# romboard_v2.net
KiCad netlist of a schematic drawn in EAGLE
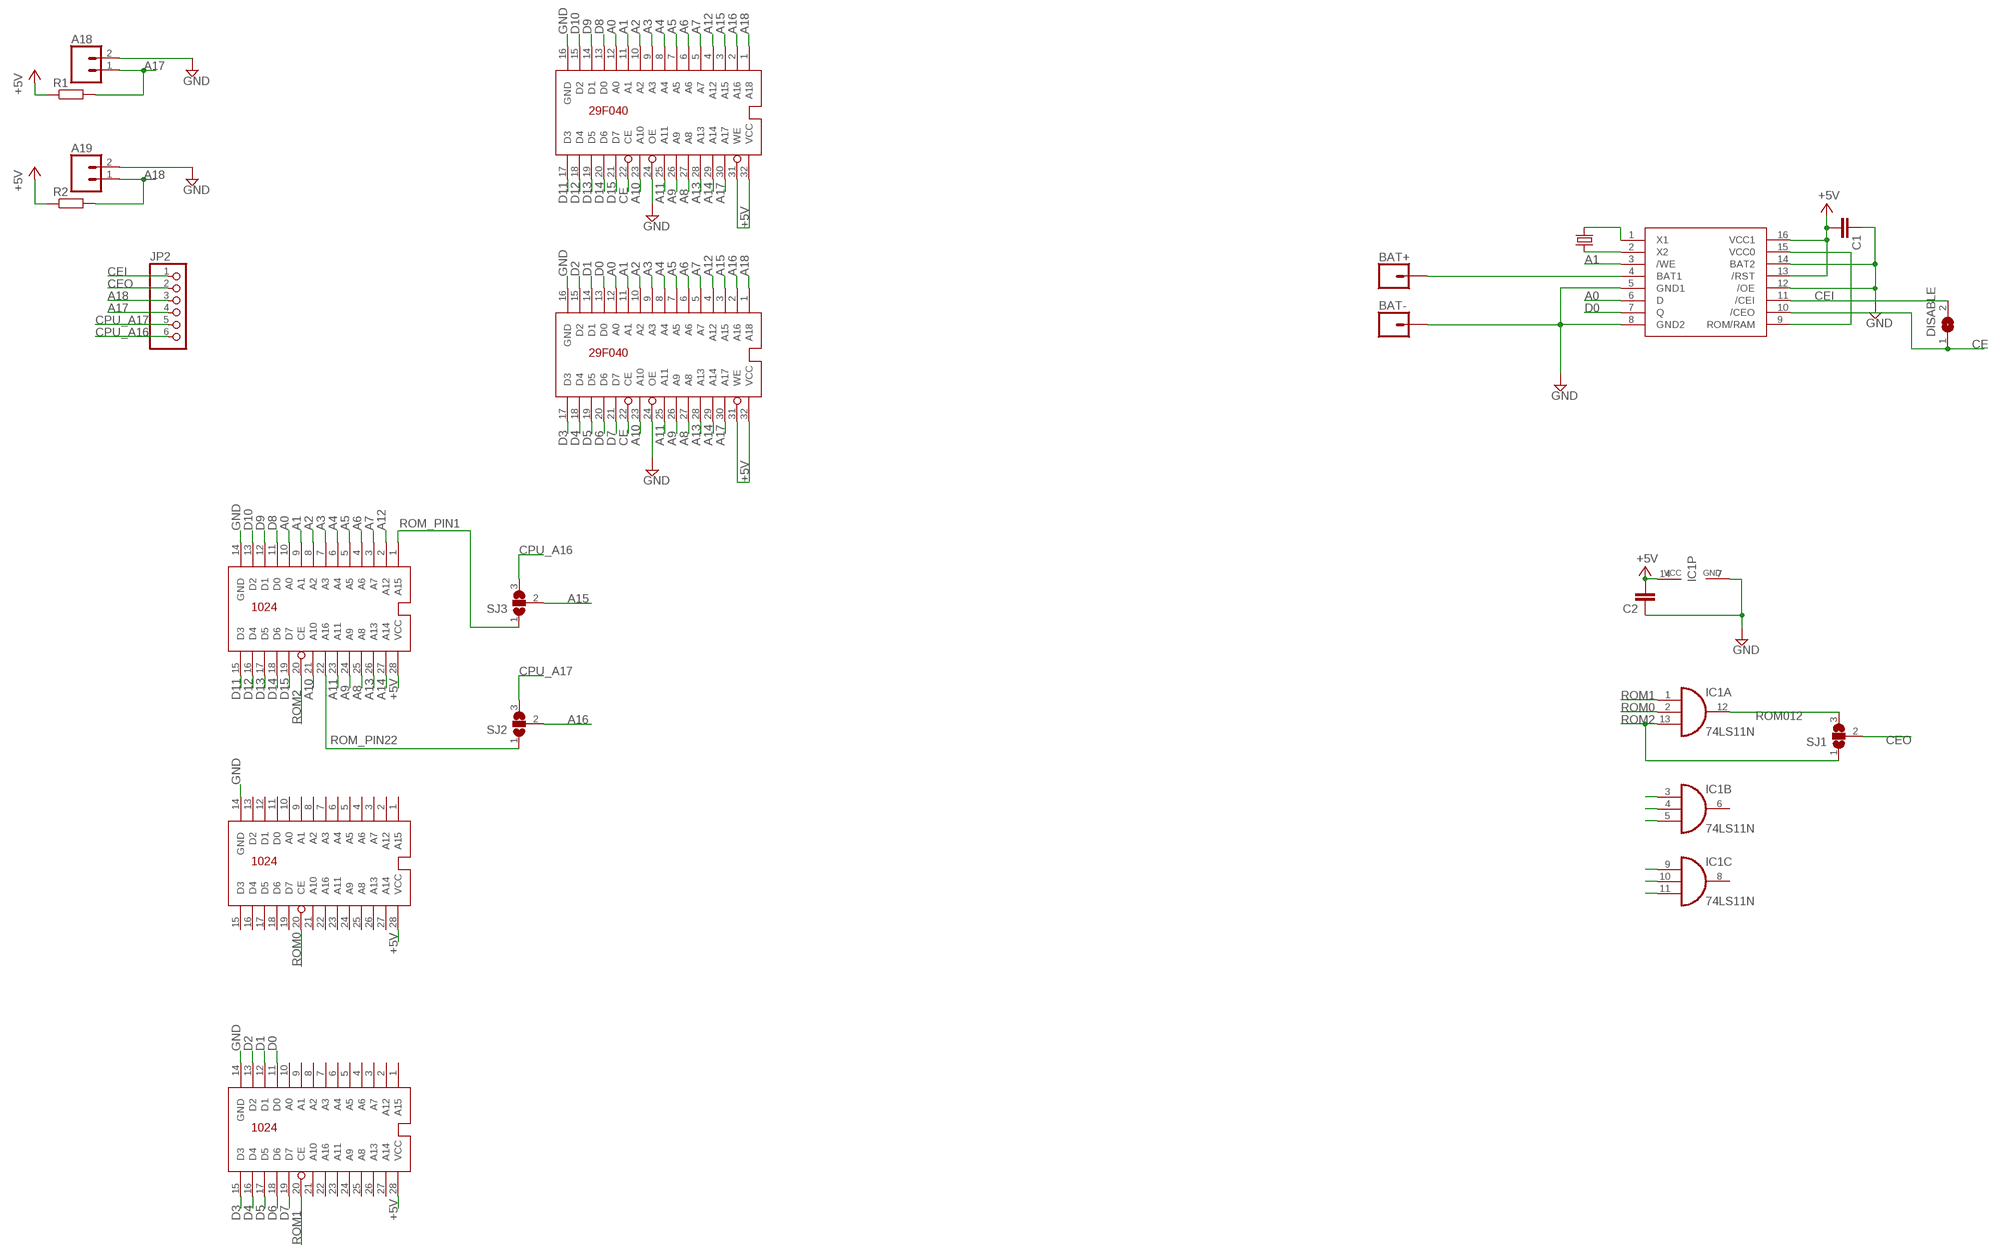
[diagram p0: schematic, sheet 1]

(export (version "E")
  (design (tool "Eeschema 10.0.6"))
  (components
    (comp (ref "32.768KHZ")
      (value "CRYSTALTC38H")
      (footprint "eagle-import:TC38H")
      (libsource (lib "eagle-import") (part "CRYSTALTC38H"))
    )
    (comp (ref "A18")
      (value "CONN_02")
      (footprint "eagle-import:1X02")
      (libsource (lib "eagle-import") (part "CONN_02"))
    )
    (comp (ref "A19")
      (value "CONN_02")
      (footprint "eagle-import:1X02")
      (libsource (lib "eagle-import") (part "CONN_02"))
    )
    (comp (ref "BAT+")
      (value "CONN_01")
      (footprint "eagle-import:1X01")
      (libsource (lib "eagle-import") (part "CONN_01"))
    )
    (comp (ref "BAT-")
      (value "CONN_01")
      (footprint "eagle-import:1X01")
      (libsource (lib "eagle-import") (part "CONN_01"))
    )
    (comp (ref "C1")
      (value "C-EU050-025X075")
      (footprint "eagle-import:C050-025X075")
      (libsource (lib "eagle-import") (part "C-EU050-025X075"))
    )
    (comp (ref "C2")
      (value "C-EU050-025X075")
      (footprint "eagle-import:C050-025X075")
      (libsource (lib "eagle-import") (part "C-EU050-025X075"))
    )
    (comp (ref "DISABLE")
      (value "SJ")
      (footprint "eagle-import:SJ")
      (libsource (lib "eagle-import") (part "SJ"))
    )
    (comp (ref "HI0_SOCKET")
      (value "ROM1024")
      (footprint "eagle-import:ROM28PIN")
      (libsource (lib "eagle-import") (part "ROM1024"))
    )
    (comp (ref "IC1")
      (value "74LS11N")
      (footprint "eagle-import:DIL14")
      (libsource (lib "eagle-import") (part "7411NLS"))
    )
    (comp (ref "JP2")
      (value "PINHD-1X6/90")
      (footprint "eagle-import:1X06_90")
      (libsource (lib "eagle-import") (part "PINHD-1X6/90"))
    )
    (comp (ref "LO2_SOCKET")
      (value "ROM1024")
      (footprint "eagle-import:ROM28PIN")
      (libsource (lib "eagle-import") (part "ROM1024"))
    )
    (comp (ref "LO2_SOCKET1")
      (value "ROM1024")
      (footprint "eagle-import:ROM28PIN")
      (libsource (lib "eagle-import") (part "ROM1024"))
    )
    (comp (ref "R1")
      (value "R-EU_0207/12")
      (footprint "eagle-import:0207_12")
      (libsource (lib "eagle-import") (part "R-EU_0207/12"))
    )
    (comp (ref "R2")
      (value "R-EU_0207/12")
      (footprint "eagle-import:0207_12")
      (libsource (lib "eagle-import") (part "R-EU_0207/12"))
    )
    (comp (ref "SJ1")
      (value "SJ2W")
      (footprint "eagle-import:SJ_2")
      (libsource (lib "eagle-import") (part "SJ2W"))
    )
    (comp (ref "SJ2")
      (value "SJ2W")
      (footprint "eagle-import:SJ_2")
      (libsource (lib "eagle-import") (part "SJ2W"))
    )
    (comp (ref "SJ3")
      (value "SJ2W")
      (footprint "eagle-import:SJ_2")
      (libsource (lib "eagle-import") (part "SJ2W"))
    )
    (comp (ref "U$1")
      (value "AM29F040")
      (footprint "eagle-import:AM29F040")
      (libsource (lib "eagle-import") (part "AM29F040"))
    )
    (comp (ref "U$2")
      (value "AM29F040")
      (footprint "eagle-import:AM29F040")
      (libsource (lib "eagle-import") (part "AM29F040"))
    )
    (comp (ref "U$4")
      (value "DS1315")
      (footprint "eagle-import:DIL16")
      (libsource (lib "eagle-import") (part "DS1315"))
    )
  )
  (nets
    (net (code "1") (name "+5V") (class "Default")
      (node (ref "C1") (pin "2") (pinfunction "2_2") (pintype "passive"))
      (node (ref "C2") (pin "2") (pinfunction "2_2") (pintype "passive"))
      (node (ref "HI0_SOCKET") (pin "28") (pinfunction "VCC_28") (pintype "bidirectional"))
      (node (ref "IC1") (pin "14") (pinfunction "VCC_14") (pintype "power_in"))
      (node (ref "LO2_SOCKET") (pin "28") (pinfunction "VCC_28") (pintype "bidirectional"))
      (node (ref "LO2_SOCKET1") (pin "28") (pinfunction "VCC_28") (pintype "bidirectional"))
      (node (ref "R1") (pin "1") (pinfunction "1_1") (pintype "passive"))
      (node (ref "R2") (pin "1") (pinfunction "1_1") (pintype "passive"))
      (node (ref "U$1") (pin "31") (pinfunction "WE_31") (pintype "bidirectional"))
      (node (ref "U$1") (pin "32") (pinfunction "VCC_32") (pintype "bidirectional"))
      (node (ref "U$2") (pin "31") (pinfunction "WE_31") (pintype "bidirectional"))
      (node (ref "U$2") (pin "32") (pinfunction "VCC_32") (pintype "bidirectional"))
      (node (ref "U$4") (pin "13") (pinfunction "/RST_13") (pintype "bidirectional"))
      (node (ref "U$4") (pin "16") (pinfunction "VCC1_16") (pintype "bidirectional"))
    )
    (net (code "2") (name "/A0") (class "Default")
      (node (ref "HI0_SOCKET") (pin "10") (pinfunction "A0_10") (pintype "bidirectional"))
      (node (ref "U$1") (pin "12") (pinfunction "A0_12") (pintype "bidirectional"))
      (node (ref "U$2") (pin "12") (pinfunction "A0_12") (pintype "bidirectional"))
      (node (ref "U$4") (pin "6") (pinfunction "D_6") (pintype "bidirectional"))
    )
    (net (code "3") (name "/A1") (class "Default")
      (node (ref "HI0_SOCKET") (pin "9") (pinfunction "A1_9") (pintype "bidirectional"))
      (node (ref "U$1") (pin "11") (pinfunction "A1_11") (pintype "bidirectional"))
      (node (ref "U$2") (pin "11") (pinfunction "A1_11") (pintype "bidirectional"))
      (node (ref "U$4") (pin "3") (pinfunction "/WE_3") (pintype "bidirectional"))
    )
    (net (code "4") (name "/A2") (class "Default")
      (node (ref "HI0_SOCKET") (pin "8") (pinfunction "A2_8") (pintype "bidirectional"))
      (node (ref "U$1") (pin "10") (pinfunction "A2_10") (pintype "bidirectional"))
      (node (ref "U$2") (pin "10") (pinfunction "A2_10") (pintype "bidirectional"))
    )
    (net (code "5") (name "/A3") (class "Default")
      (node (ref "HI0_SOCKET") (pin "7") (pinfunction "A3_7") (pintype "bidirectional"))
      (node (ref "U$1") (pin "9") (pinfunction "A3_9") (pintype "bidirectional"))
      (node (ref "U$2") (pin "9") (pinfunction "A3_9") (pintype "bidirectional"))
    )
    (net (code "6") (name "/A4") (class "Default")
      (node (ref "HI0_SOCKET") (pin "6") (pinfunction "A4_6") (pintype "bidirectional"))
      (node (ref "U$1") (pin "8") (pinfunction "A4_8") (pintype "bidirectional"))
      (node (ref "U$2") (pin "8") (pinfunction "A4_8") (pintype "bidirectional"))
    )
    (net (code "7") (name "/A5") (class "Default")
      (node (ref "HI0_SOCKET") (pin "5") (pinfunction "A5_5") (pintype "bidirectional"))
      (node (ref "U$1") (pin "7") (pinfunction "A5_7") (pintype "bidirectional"))
      (node (ref "U$2") (pin "7") (pinfunction "A5_7") (pintype "bidirectional"))
    )
    (net (code "8") (name "/A6") (class "Default")
      (node (ref "HI0_SOCKET") (pin "4") (pinfunction "A6_4") (pintype "bidirectional"))
      (node (ref "U$1") (pin "6") (pinfunction "A6_6") (pintype "bidirectional"))
      (node (ref "U$2") (pin "6") (pinfunction "A6_6") (pintype "bidirectional"))
    )
    (net (code "9") (name "/A7") (class "Default")
      (node (ref "HI0_SOCKET") (pin "3") (pinfunction "A7_3") (pintype "bidirectional"))
      (node (ref "U$1") (pin "5") (pinfunction "A7_5") (pintype "bidirectional"))
      (node (ref "U$2") (pin "5") (pinfunction "A7_5") (pintype "bidirectional"))
    )
    (net (code "10") (name "/A8") (class "Default")
      (node (ref "HI0_SOCKET") (pin "25") (pinfunction "A8_25") (pintype "bidirectional"))
      (node (ref "U$1") (pin "27") (pinfunction "A8_27") (pintype "bidirectional"))
      (node (ref "U$2") (pin "27") (pinfunction "A8_27") (pintype "bidirectional"))
    )
    (net (code "11") (name "/A9") (class "Default")
      (node (ref "HI0_SOCKET") (pin "24") (pinfunction "A9_24") (pintype "bidirectional"))
      (node (ref "U$1") (pin "26") (pinfunction "A9_26") (pintype "bidirectional"))
      (node (ref "U$2") (pin "26") (pinfunction "A9_26") (pintype "bidirectional"))
    )
    (net (code "12") (name "/A10") (class "Default")
      (node (ref "HI0_SOCKET") (pin "21") (pinfunction "A10_21") (pintype "bidirectional"))
      (node (ref "U$1") (pin "23") (pinfunction "A10_23") (pintype "bidirectional"))
      (node (ref "U$2") (pin "23") (pinfunction "A10_23") (pintype "bidirectional"))
    )
    (net (code "13") (name "/A11") (class "Default")
      (node (ref "HI0_SOCKET") (pin "23") (pinfunction "A11_23") (pintype "bidirectional"))
      (node (ref "U$1") (pin "25") (pinfunction "A11_25") (pintype "bidirectional"))
      (node (ref "U$2") (pin "25") (pinfunction "A11_25") (pintype "bidirectional"))
    )
    (net (code "14") (name "/A12") (class "Default")
      (node (ref "HI0_SOCKET") (pin "2") (pinfunction "A12_2") (pintype "bidirectional"))
      (node (ref "U$1") (pin "4") (pinfunction "A12_4") (pintype "bidirectional"))
      (node (ref "U$2") (pin "4") (pinfunction "A12_4") (pintype "bidirectional"))
    )
    (net (code "15") (name "/A13") (class "Default")
      (node (ref "HI0_SOCKET") (pin "26") (pinfunction "A13_26") (pintype "bidirectional"))
      (node (ref "U$1") (pin "28") (pinfunction "A13_28") (pintype "bidirectional"))
      (node (ref "U$2") (pin "28") (pinfunction "A13_28") (pintype "bidirectional"))
    )
    (net (code "16") (name "/A14") (class "Default")
      (node (ref "HI0_SOCKET") (pin "27") (pinfunction "A14_27") (pintype "bidirectional"))
      (node (ref "U$1") (pin "29") (pinfunction "A14_29") (pintype "bidirectional"))
      (node (ref "U$2") (pin "29") (pinfunction "A14_29") (pintype "bidirectional"))
    )
    (net (code "17") (name "/A15") (class "Default")
      (node (ref "SJ3") (pin "2") (pinfunction "2_2") (pintype "passive"))
      (node (ref "U$1") (pin "3") (pinfunction "A15_3") (pintype "bidirectional"))
      (node (ref "U$2") (pin "3") (pinfunction "A15_3") (pintype "bidirectional"))
    )
    (net (code "18") (name "/A16") (class "Default")
      (node (ref "SJ2") (pin "2") (pinfunction "2_2") (pintype "passive"))
      (node (ref "U$1") (pin "2") (pinfunction "A16_2") (pintype "bidirectional"))
      (node (ref "U$2") (pin "2") (pinfunction "A16_2") (pintype "bidirectional"))
    )
    (net (code "19") (name "/A17") (class "Default")
      (node (ref "A18") (pin "1") (pinfunction "1_1") (pintype "passive"))
      (node (ref "JP2") (pin "4") (pinfunction "4_4") (pintype "passive"))
      (node (ref "R1") (pin "2") (pinfunction "2_2") (pintype "passive"))
      (node (ref "U$1") (pin "30") (pinfunction "A17_30") (pintype "bidirectional"))
      (node (ref "U$2") (pin "30") (pinfunction "A17_30") (pintype "bidirectional"))
    )
    (net (code "20") (name "/A18") (class "Default")
      (node (ref "A19") (pin "1") (pinfunction "1_1") (pintype "passive"))
      (node (ref "JP2") (pin "3") (pinfunction "3_3") (pintype "passive"))
      (node (ref "R2") (pin "2") (pinfunction "2_2") (pintype "passive"))
      (node (ref "U$1") (pin "1") (pinfunction "A18_1") (pintype "bidirectional"))
      (node (ref "U$2") (pin "1") (pinfunction "A18_1") (pintype "bidirectional"))
    )
    (net (code "21") (name "/CE") (class "Default")
      (node (ref "DISABLE") (pin "1") (pinfunction "1_1") (pintype "passive"))
      (node (ref "U$1") (pin "22") (pinfunction "CE_22") (pintype "bidirectional"))
      (node (ref "U$2") (pin "22") (pinfunction "CE_22") (pintype "bidirectional"))
      (node (ref "U$4") (pin "10") (pinfunction "/CEO_10") (pintype "bidirectional"))
    )
    (net (code "22") (name "/CEI") (class "Default")
      (node (ref "DISABLE") (pin "2") (pinfunction "2_2") (pintype "passive"))
      (node (ref "JP2") (pin "1") (pinfunction "1_1") (pintype "passive"))
      (node (ref "U$4") (pin "11") (pinfunction "/CEI_11") (pintype "bidirectional"))
    )
    (net (code "23") (name "/CEO") (class "Default")
      (node (ref "JP2") (pin "2") (pinfunction "2_2") (pintype "passive"))
      (node (ref "SJ1") (pin "2") (pinfunction "2_2") (pintype "passive"))
    )
    (net (code "24") (name "/CPU_A16") (class "Default")
      (node (ref "JP2") (pin "6") (pinfunction "6_6") (pintype "passive"))
      (node (ref "SJ3") (pin "3") (pinfunction "3_3") (pintype "passive"))
    )
    (net (code "25") (name "/CPU_A17") (class "Default")
      (node (ref "JP2") (pin "5") (pinfunction "5_5") (pintype "passive"))
      (node (ref "SJ2") (pin "3") (pinfunction "3_3") (pintype "passive"))
    )
    (net (code "26") (name "/D0") (class "Default")
      (node (ref "LO2_SOCKET") (pin "11") (pinfunction "D0_11") (pintype "bidirectional"))
      (node (ref "U$1") (pin "13") (pinfunction "D0_13") (pintype "bidirectional"))
      (node (ref "U$4") (pin "7") (pinfunction "Q_7") (pintype "bidirectional"))
    )
    (net (code "27") (name "/D1") (class "Default")
      (node (ref "LO2_SOCKET") (pin "12") (pinfunction "D1_12") (pintype "bidirectional"))
      (node (ref "U$1") (pin "14") (pinfunction "D1_14") (pintype "bidirectional"))
    )
    (net (code "28") (name "/D2") (class "Default")
      (node (ref "LO2_SOCKET") (pin "13") (pinfunction "D2_13") (pintype "bidirectional"))
      (node (ref "U$1") (pin "15") (pinfunction "D2_15") (pintype "bidirectional"))
    )
    (net (code "29") (name "/D3") (class "Default")
      (node (ref "LO2_SOCKET") (pin "15") (pinfunction "D3_15") (pintype "bidirectional"))
      (node (ref "U$1") (pin "17") (pinfunction "D3_17") (pintype "bidirectional"))
    )
    (net (code "30") (name "/D4") (class "Default")
      (node (ref "LO2_SOCKET") (pin "16") (pinfunction "D4_16") (pintype "bidirectional"))
      (node (ref "U$1") (pin "18") (pinfunction "D4_18") (pintype "bidirectional"))
    )
    (net (code "31") (name "/D5") (class "Default")
      (node (ref "LO2_SOCKET") (pin "17") (pinfunction "D5_17") (pintype "bidirectional"))
      (node (ref "U$1") (pin "19") (pinfunction "D5_19") (pintype "bidirectional"))
    )
    (net (code "32") (name "/D6") (class "Default")
      (node (ref "LO2_SOCKET") (pin "18") (pinfunction "D6_18") (pintype "bidirectional"))
      (node (ref "U$1") (pin "20") (pinfunction "D6_20") (pintype "bidirectional"))
    )
    (net (code "33") (name "/D7") (class "Default")
      (node (ref "LO2_SOCKET") (pin "19") (pinfunction "D7_19") (pintype "bidirectional"))
      (node (ref "U$1") (pin "21") (pinfunction "D7_21") (pintype "bidirectional"))
    )
    (net (code "34") (name "/D8") (class "Default")
      (node (ref "HI0_SOCKET") (pin "11") (pinfunction "D0_11") (pintype "bidirectional"))
      (node (ref "U$2") (pin "13") (pinfunction "D0_13") (pintype "bidirectional"))
    )
    (net (code "35") (name "/D9") (class "Default")
      (node (ref "HI0_SOCKET") (pin "12") (pinfunction "D1_12") (pintype "bidirectional"))
      (node (ref "U$2") (pin "14") (pinfunction "D1_14") (pintype "bidirectional"))
    )
    (net (code "36") (name "/D10") (class "Default")
      (node (ref "HI0_SOCKET") (pin "13") (pinfunction "D2_13") (pintype "bidirectional"))
      (node (ref "U$2") (pin "15") (pinfunction "D2_15") (pintype "bidirectional"))
    )
    (net (code "37") (name "/D11") (class "Default")
      (node (ref "HI0_SOCKET") (pin "15") (pinfunction "D3_15") (pintype "bidirectional"))
      (node (ref "U$2") (pin "17") (pinfunction "D3_17") (pintype "bidirectional"))
    )
    (net (code "38") (name "/D12") (class "Default")
      (node (ref "HI0_SOCKET") (pin "16") (pinfunction "D4_16") (pintype "bidirectional"))
      (node (ref "U$2") (pin "18") (pinfunction "D4_18") (pintype "bidirectional"))
    )
    (net (code "39") (name "/D13") (class "Default")
      (node (ref "HI0_SOCKET") (pin "17") (pinfunction "D5_17") (pintype "bidirectional"))
      (node (ref "U$2") (pin "19") (pinfunction "D5_19") (pintype "bidirectional"))
    )
    (net (code "40") (name "/D14") (class "Default")
      (node (ref "HI0_SOCKET") (pin "18") (pinfunction "D6_18") (pintype "bidirectional"))
      (node (ref "U$2") (pin "20") (pinfunction "D6_20") (pintype "bidirectional"))
    )
    (net (code "41") (name "/D15") (class "Default")
      (node (ref "HI0_SOCKET") (pin "19") (pinfunction "D7_19") (pintype "bidirectional"))
      (node (ref "U$2") (pin "21") (pinfunction "D7_21") (pintype "bidirectional"))
    )
    (net (code "42") (name "/ROM0") (class "Default")
      (node (ref "IC1") (pin "2") (pinfunction "I1_2") (pintype "input"))
      (node (ref "LO2_SOCKET1") (pin "20") (pinfunction "CE_20") (pintype "bidirectional"))
    )
    (net (code "43") (name "/ROM1") (class "Default")
      (node (ref "IC1") (pin "1") (pinfunction "I0_1") (pintype "input"))
      (node (ref "LO2_SOCKET") (pin "20") (pinfunction "CE_20") (pintype "bidirectional"))
    )
    (net (code "44") (name "/ROM2") (class "Default")
      (node (ref "HI0_SOCKET") (pin "20") (pinfunction "CE_20") (pintype "bidirectional"))
      (node (ref "IC1") (pin "13") (pinfunction "I2_13") (pintype "input"))
      (node (ref "SJ1") (pin "1") (pinfunction "1_1") (pintype "passive"))
    )
    (net (code "45") (name "/ROM012") (class "Default")
      (node (ref "IC1") (pin "12") (pinfunction "O_12") (pintype "output"))
      (node (ref "SJ1") (pin "3") (pinfunction "3_3") (pintype "passive"))
    )
    (net (code "46") (name "/ROM_PIN1") (class "Default")
      (node (ref "HI0_SOCKET") (pin "1") (pinfunction "A15_1") (pintype "bidirectional"))
      (node (ref "SJ3") (pin "1") (pinfunction "1_1") (pintype "passive"))
    )
    (net (code "47") (name "/ROM_PIN22") (class "Default")
      (node (ref "HI0_SOCKET") (pin "22") (pinfunction "A16_22") (pintype "bidirectional"))
      (node (ref "SJ2") (pin "1") (pinfunction "1_1") (pintype "passive"))
    )
    (net (code "48") (name "GND") (class "Default")
      (node (ref "A18") (pin "2") (pinfunction "2_2") (pintype "passive"))
      (node (ref "A19") (pin "2") (pinfunction "2_2") (pintype "passive"))
      (node (ref "BAT-") (pin "1") (pinfunction "1_1") (pintype "passive"))
      (node (ref "C1") (pin "1") (pinfunction "1_1") (pintype "passive"))
      (node (ref "C2") (pin "1") (pinfunction "1_1") (pintype "passive"))
      (node (ref "HI0_SOCKET") (pin "14") (pinfunction "GND_14") (pintype "bidirectional"))
      (node (ref "IC1") (pin "7") (pinfunction "GND_7") (pintype "power_in"))
      (node (ref "LO2_SOCKET") (pin "14") (pinfunction "GND_14") (pintype "bidirectional"))
      (node (ref "LO2_SOCKET1") (pin "14") (pinfunction "GND_14") (pintype "bidirectional"))
      (node (ref "U$1") (pin "16") (pinfunction "GND_16") (pintype "bidirectional"))
      (node (ref "U$1") (pin "24") (pinfunction "OE_24") (pintype "bidirectional"))
      (node (ref "U$2") (pin "16") (pinfunction "GND_16") (pintype "bidirectional"))
      (node (ref "U$2") (pin "24") (pinfunction "OE_24") (pintype "bidirectional"))
      (node (ref "U$4") (pin "12") (pinfunction "/OE_12") (pintype "bidirectional"))
      (node (ref "U$4") (pin "14") (pinfunction "BAT2_14") (pintype "bidirectional"))
      (node (ref "U$4") (pin "5") (pinfunction "GND1_5") (pintype "bidirectional"))
      (node (ref "U$4") (pin "8") (pinfunction "GND2_8") (pintype "bidirectional"))
    )
    (net (code "49") (name "Net-(U$4-BAT1)") (class "Default")
      (node (ref "BAT+") (pin "1") (pinfunction "1_1") (pintype "passive"))
      (node (ref "U$4") (pin "4") (pinfunction "BAT1_4") (pintype "bidirectional"))
    )
    (net (code "50") (name "Net-(U$4-ROM{slash}RAM)") (class "Default")
      (node (ref "U$4") (pin "15") (pinfunction "VCC0_15") (pintype "bidirectional"))
      (node (ref "U$4") (pin "9") (pinfunction "ROM/RAM_9") (pintype "bidirectional"))
    )
    (net (code "51") (name "Net-(U$4-X1)") (class "Default")
      (node (ref "32.768KHZ") (pin "2") (pinfunction "2_2") (pintype "passive"))
      (node (ref "U$4") (pin "1") (pinfunction "X1_1") (pintype "bidirectional"))
    )
    (net (code "52") (name "Net-(U$4-X2)") (class "Default")
      (node (ref "32.768KHZ") (pin "1") (pinfunction "1_1") (pintype "passive"))
      (node (ref "U$4") (pin "2") (pinfunction "X2_2") (pintype "bidirectional"))
    )
    (net (code "53") (name "unconnected-(IC1B-I0-Pad3)") (class "Default")
      (node (ref "IC1") (pin "3") (pinfunction "I0_3") (pintype "input"))
    )
    (net (code "54") (name "unconnected-(IC1B-I1-Pad4)") (class "Default")
      (node (ref "IC1") (pin "4") (pinfunction "I1_4") (pintype "input"))
    )
    (net (code "55") (name "unconnected-(IC1B-I2-Pad5)") (class "Default")
      (node (ref "IC1") (pin "5") (pinfunction "I2_5") (pintype "input"))
    )
    (net (code "56") (name "unconnected-(IC1B-O-Pad6)") (class "Default")
      (node (ref "IC1") (pin "6") (pinfunction "O_6") (pintype "output"))
    )
    (net (code "57") (name "unconnected-(IC1C-I0-Pad9)") (class "Default")
      (node (ref "IC1") (pin "9") (pinfunction "I0_9") (pintype "input"))
    )
    (net (code "58") (name "unconnected-(IC1C-I1-Pad10)") (class "Default")
      (node (ref "IC1") (pin "10") (pinfunction "I1_10") (pintype "input"))
    )
    (net (code "59") (name "unconnected-(IC1C-I2-Pad11)") (class "Default")
      (node (ref "IC1") (pin "11") (pinfunction "I2_11") (pintype "input"))
    )
    (net (code "60") (name "unconnected-(IC1C-O-Pad8)") (class "Default")
      (node (ref "IC1") (pin "8") (pinfunction "O_8") (pintype "output"))
    )
    (net (code "61") (name "unconnected-(LO2_SOCKET-A0-Pad10)") (class "Default")
      (node (ref "LO2_SOCKET") (pin "10") (pinfunction "A0_10") (pintype "bidirectional"))
    )
    (net (code "62") (name "unconnected-(LO2_SOCKET-A1-Pad9)") (class "Default")
      (node (ref "LO2_SOCKET") (pin "9") (pinfunction "A1_9") (pintype "bidirectional"))
    )
    (net (code "63") (name "unconnected-(LO2_SOCKET-A2-Pad8)") (class "Default")
      (node (ref "LO2_SOCKET") (pin "8") (pinfunction "A2_8") (pintype "bidirectional"))
    )
    (net (code "64") (name "unconnected-(LO2_SOCKET-A3-Pad7)") (class "Default")
      (node (ref "LO2_SOCKET") (pin "7") (pinfunction "A3_7") (pintype "bidirectional"))
    )
    (net (code "65") (name "unconnected-(LO2_SOCKET-A4-Pad6)") (class "Default")
      (node (ref "LO2_SOCKET") (pin "6") (pinfunction "A4_6") (pintype "bidirectional"))
    )
    (net (code "66") (name "unconnected-(LO2_SOCKET-A5-Pad5)") (class "Default")
      (node (ref "LO2_SOCKET") (pin "5") (pinfunction "A5_5") (pintype "bidirectional"))
    )
    (net (code "67") (name "unconnected-(LO2_SOCKET-A6-Pad4)") (class "Default")
      (node (ref "LO2_SOCKET") (pin "4") (pinfunction "A6_4") (pintype "bidirectional"))
    )
    (net (code "68") (name "unconnected-(LO2_SOCKET-A7-Pad3)") (class "Default")
      (node (ref "LO2_SOCKET") (pin "3") (pinfunction "A7_3") (pintype "bidirectional"))
    )
    (net (code "69") (name "unconnected-(LO2_SOCKET-A8-Pad25)") (class "Default")
      (node (ref "LO2_SOCKET") (pin "25") (pinfunction "A8_25") (pintype "bidirectional"))
    )
    (net (code "70") (name "unconnected-(LO2_SOCKET-A9-Pad24)") (class "Default")
      (node (ref "LO2_SOCKET") (pin "24") (pinfunction "A9_24") (pintype "bidirectional"))
    )
    (net (code "71") (name "unconnected-(LO2_SOCKET-A10-Pad21)") (class "Default")
      (node (ref "LO2_SOCKET") (pin "21") (pinfunction "A10_21") (pintype "bidirectional"))
    )
    (net (code "72") (name "unconnected-(LO2_SOCKET-A11-Pad23)") (class "Default")
      (node (ref "LO2_SOCKET") (pin "23") (pinfunction "A11_23") (pintype "bidirectional"))
    )
    (net (code "73") (name "unconnected-(LO2_SOCKET-A12-Pad2)") (class "Default")
      (node (ref "LO2_SOCKET") (pin "2") (pinfunction "A12_2") (pintype "bidirectional"))
    )
    (net (code "74") (name "unconnected-(LO2_SOCKET-A13-Pad26)") (class "Default")
      (node (ref "LO2_SOCKET") (pin "26") (pinfunction "A13_26") (pintype "bidirectional"))
    )
    (net (code "75") (name "unconnected-(LO2_SOCKET-A14-Pad27)") (class "Default")
      (node (ref "LO2_SOCKET") (pin "27") (pinfunction "A14_27") (pintype "bidirectional"))
    )
    (net (code "76") (name "unconnected-(LO2_SOCKET-A15-Pad1)") (class "Default")
      (node (ref "LO2_SOCKET") (pin "1") (pinfunction "A15_1") (pintype "bidirectional"))
    )
    (net (code "77") (name "unconnected-(LO2_SOCKET-A16-Pad22)") (class "Default")
      (node (ref "LO2_SOCKET") (pin "22") (pinfunction "A16_22") (pintype "bidirectional"))
    )
    (net (code "78") (name "unconnected-(LO2_SOCKET1-A0-Pad10)") (class "Default")
      (node (ref "LO2_SOCKET1") (pin "10") (pinfunction "A0_10") (pintype "bidirectional"))
    )
    (net (code "79") (name "unconnected-(LO2_SOCKET1-A1-Pad9)") (class "Default")
      (node (ref "LO2_SOCKET1") (pin "9") (pinfunction "A1_9") (pintype "bidirectional"))
    )
    (net (code "80") (name "unconnected-(LO2_SOCKET1-A2-Pad8)") (class "Default")
      (node (ref "LO2_SOCKET1") (pin "8") (pinfunction "A2_8") (pintype "bidirectional"))
    )
    (net (code "81") (name "unconnected-(LO2_SOCKET1-A3-Pad7)") (class "Default")
      (node (ref "LO2_SOCKET1") (pin "7") (pinfunction "A3_7") (pintype "bidirectional"))
    )
    (net (code "82") (name "unconnected-(LO2_SOCKET1-A4-Pad6)") (class "Default")
      (node (ref "LO2_SOCKET1") (pin "6") (pinfunction "A4_6") (pintype "bidirectional"))
    )
    (net (code "83") (name "unconnected-(LO2_SOCKET1-A5-Pad5)") (class "Default")
      (node (ref "LO2_SOCKET1") (pin "5") (pinfunction "A5_5") (pintype "bidirectional"))
    )
    (net (code "84") (name "unconnected-(LO2_SOCKET1-A6-Pad4)") (class "Default")
      (node (ref "LO2_SOCKET1") (pin "4") (pinfunction "A6_4") (pintype "bidirectional"))
    )
    (net (code "85") (name "unconnected-(LO2_SOCKET1-A7-Pad3)") (class "Default")
      (node (ref "LO2_SOCKET1") (pin "3") (pinfunction "A7_3") (pintype "bidirectional"))
    )
    (net (code "86") (name "unconnected-(LO2_SOCKET1-A8-Pad25)") (class "Default")
      (node (ref "LO2_SOCKET1") (pin "25") (pinfunction "A8_25") (pintype "bidirectional"))
    )
    (net (code "87") (name "unconnected-(LO2_SOCKET1-A9-Pad24)") (class "Default")
      (node (ref "LO2_SOCKET1") (pin "24") (pinfunction "A9_24") (pintype "bidirectional"))
    )
    (net (code "88") (name "unconnected-(LO2_SOCKET1-A10-Pad21)") (class "Default")
      (node (ref "LO2_SOCKET1") (pin "21") (pinfunction "A10_21") (pintype "bidirectional"))
    )
    (net (code "89") (name "unconnected-(LO2_SOCKET1-A11-Pad23)") (class "Default")
      (node (ref "LO2_SOCKET1") (pin "23") (pinfunction "A11_23") (pintype "bidirectional"))
    )
    (net (code "90") (name "unconnected-(LO2_SOCKET1-A12-Pad2)") (class "Default")
      (node (ref "LO2_SOCKET1") (pin "2") (pinfunction "A12_2") (pintype "bidirectional"))
    )
    (net (code "91") (name "unconnected-(LO2_SOCKET1-A13-Pad26)") (class "Default")
      (node (ref "LO2_SOCKET1") (pin "26") (pinfunction "A13_26") (pintype "bidirectional"))
    )
    (net (code "92") (name "unconnected-(LO2_SOCKET1-A14-Pad27)") (class "Default")
      (node (ref "LO2_SOCKET1") (pin "27") (pinfunction "A14_27") (pintype "bidirectional"))
    )
    (net (code "93") (name "unconnected-(LO2_SOCKET1-A15-Pad1)") (class "Default")
      (node (ref "LO2_SOCKET1") (pin "1") (pinfunction "A15_1") (pintype "bidirectional"))
    )
    (net (code "94") (name "unconnected-(LO2_SOCKET1-A16-Pad22)") (class "Default")
      (node (ref "LO2_SOCKET1") (pin "22") (pinfunction "A16_22") (pintype "bidirectional"))
    )
    (net (code "95") (name "unconnected-(LO2_SOCKET1-D0-Pad11)") (class "Default")
      (node (ref "LO2_SOCKET1") (pin "11") (pinfunction "D0_11") (pintype "bidirectional"))
    )
    (net (code "96") (name "unconnected-(LO2_SOCKET1-D1-Pad12)") (class "Default")
      (node (ref "LO2_SOCKET1") (pin "12") (pinfunction "D1_12") (pintype "bidirectional"))
    )
    (net (code "97") (name "unconnected-(LO2_SOCKET1-D2-Pad13)") (class "Default")
      (node (ref "LO2_SOCKET1") (pin "13") (pinfunction "D2_13") (pintype "bidirectional"))
    )
    (net (code "98") (name "unconnected-(LO2_SOCKET1-D3-Pad15)") (class "Default")
      (node (ref "LO2_SOCKET1") (pin "15") (pinfunction "D3_15") (pintype "bidirectional"))
    )
    (net (code "99") (name "unconnected-(LO2_SOCKET1-D4-Pad16)") (class "Default")
      (node (ref "LO2_SOCKET1") (pin "16") (pinfunction "D4_16") (pintype "bidirectional"))
    )
    (net (code "100") (name "unconnected-(LO2_SOCKET1-D5-Pad17)") (class "Default")
      (node (ref "LO2_SOCKET1") (pin "17") (pinfunction "D5_17") (pintype "bidirectional"))
    )
    (net (code "101") (name "unconnected-(LO2_SOCKET1-D6-Pad18)") (class "Default")
      (node (ref "LO2_SOCKET1") (pin "18") (pinfunction "D6_18") (pintype "bidirectional"))
    )
    (net (code "102") (name "unconnected-(LO2_SOCKET1-D7-Pad19)") (class "Default")
      (node (ref "LO2_SOCKET1") (pin "19") (pinfunction "D7_19") (pintype "bidirectional"))
    )
  )
)
